# ModuloSlave.net
KiCad netlist of a schematic drawn in EAGLE
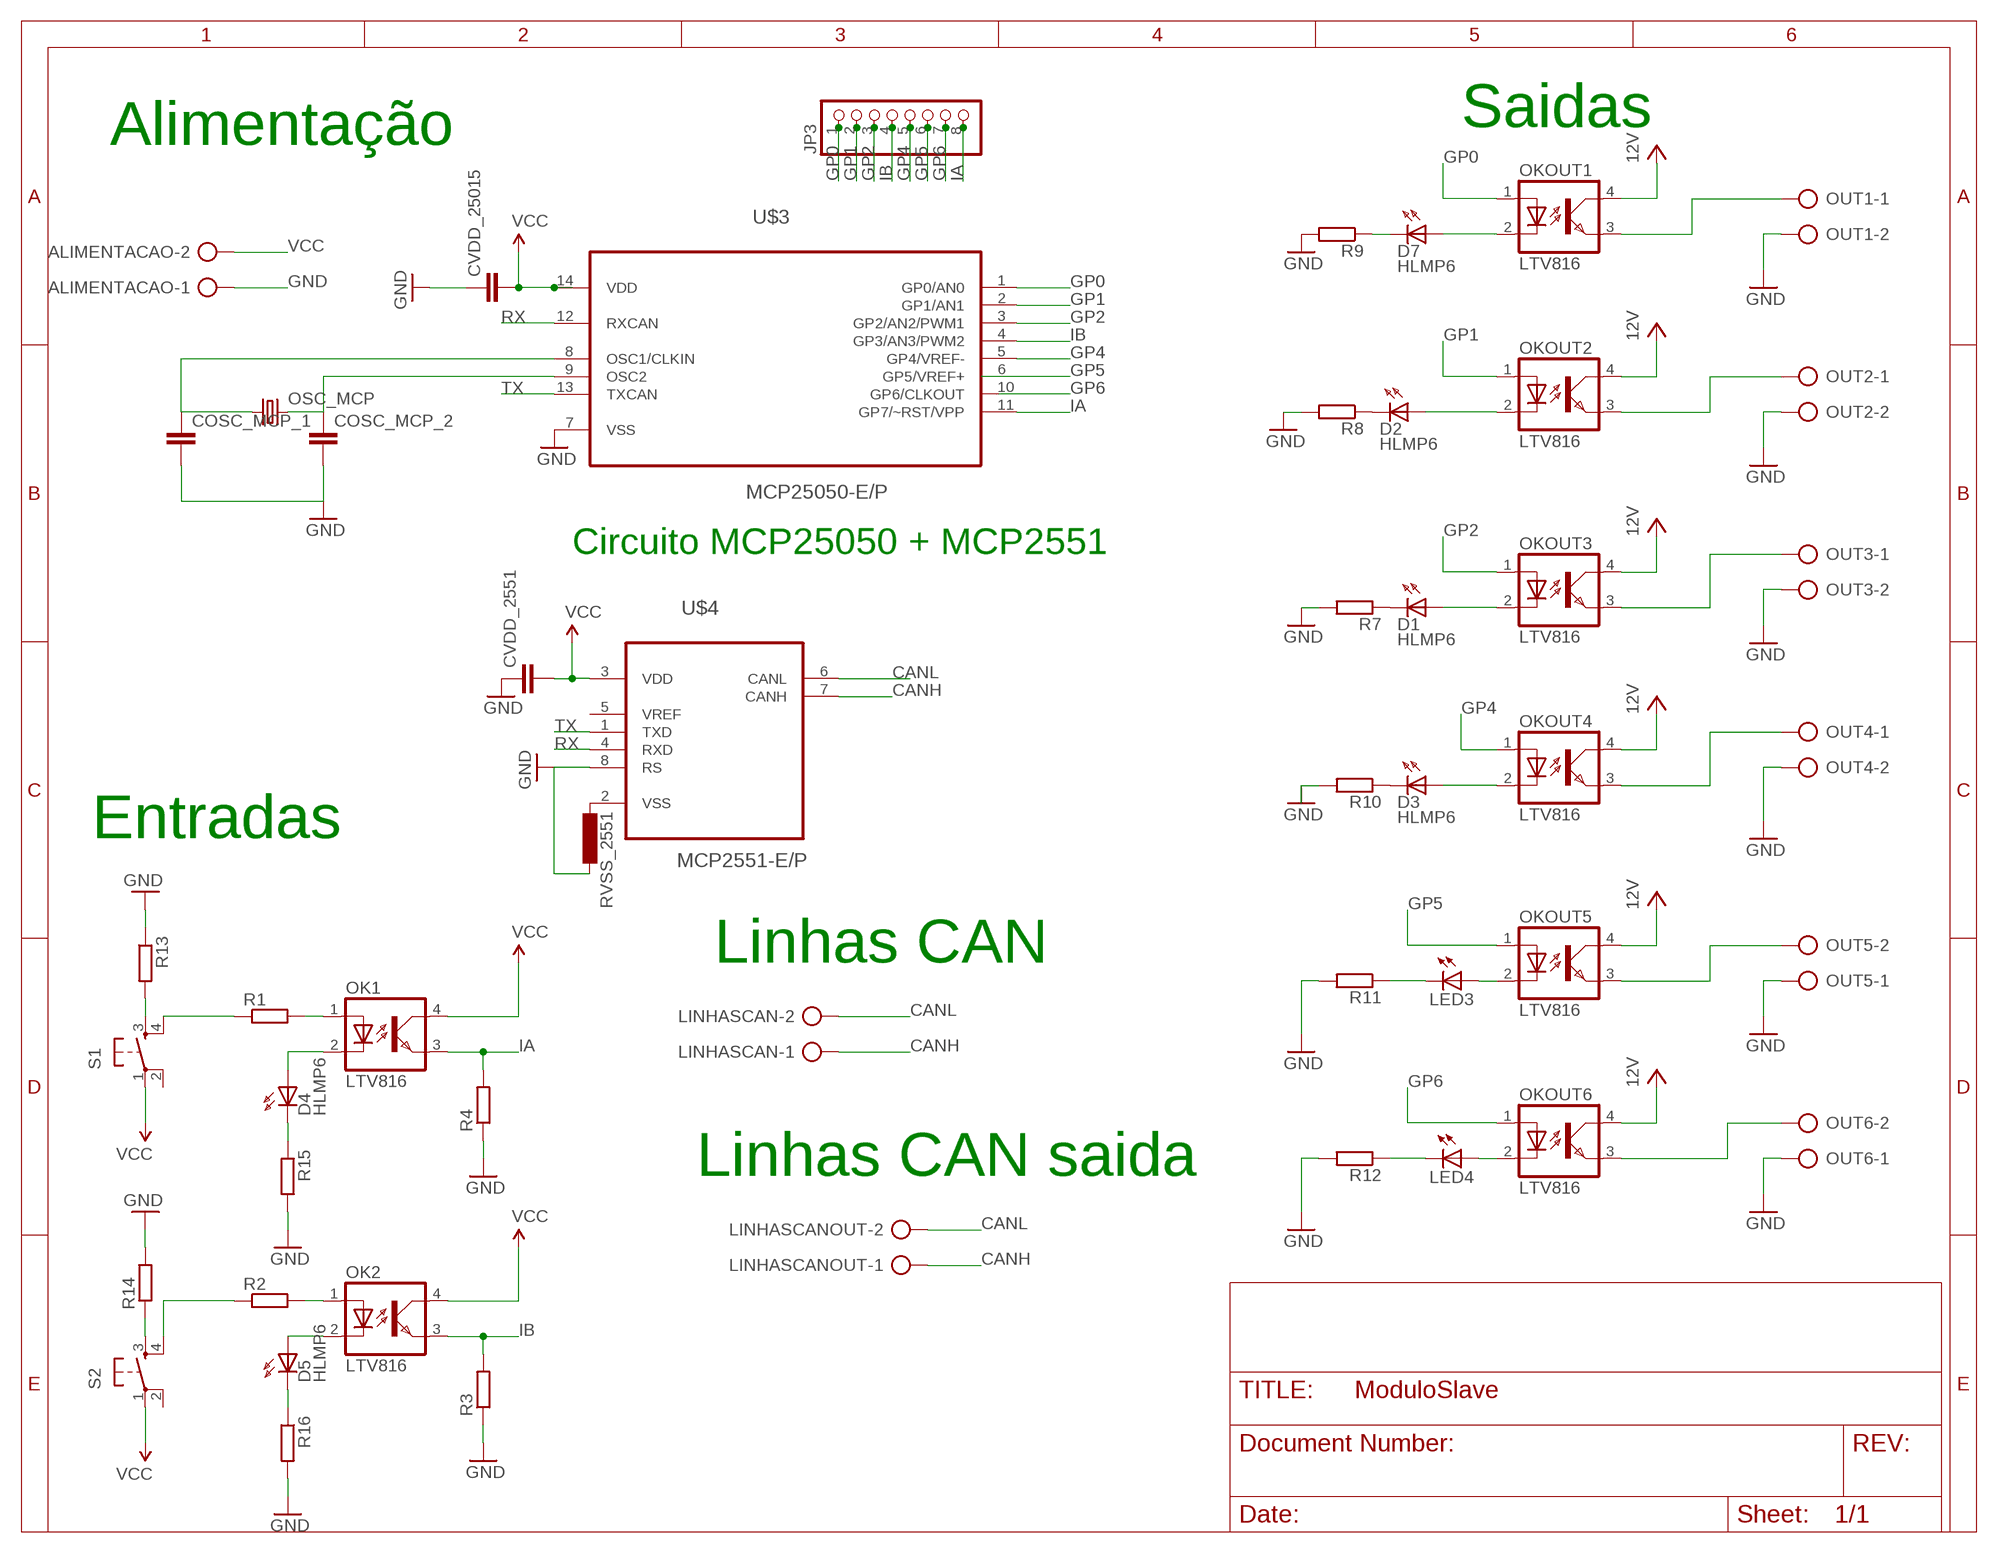
[diagram p0: schematic, sheet 1]

(export (version "E")
  (design (tool "Eeschema 10.0.6"))
  (components
    (comp (ref "ALIMENTACAO")
      (value "AK300/2")
      (footprint "eagle-import:AK300_2")
      (libsource (lib "eagle-import") (part "AK300/2"))
    )
    (comp (ref "COSC_MCP_1")
      (value "CAP_")
      (footprint "eagle-import:AXIAL-5MM")
      (libsource (lib "eagle-import") (part "CAP_"))
    )
    (comp (ref "COSC_MCP_2")
      (value "CAP_")
      (footprint "eagle-import:AXIAL-5MM")
      (libsource (lib "eagle-import") (part "CAP_"))
    )
    (comp (ref "CVDD_2551")
      (value "CAP_")
      (footprint "eagle-import:AXIAL-5MM")
      (libsource (lib "eagle-import") (part "CAP_"))
    )
    (comp (ref "CVDD_25015")
      (value "CAP_")
      (footprint "eagle-import:AXIAL-5MM")
      (libsource (lib "eagle-import") (part "CAP_"))
    )
    (comp (ref "D1")
      (value "HLMP6")
      (footprint "eagle-import:HLMP6")
      (fields (field (name "MF") "AGILENT TECHNOLOGIES") (field (name "MPN") "HLMP-6500"))
      (libsource (lib "eagle-import") (part "HLMP6"))
    )
    (comp (ref "D2")
      (value "HLMP6")
      (footprint "eagle-import:HLMP6")
      (fields (field (name "MF") "AGILENT TECHNOLOGIES") (field (name "MPN") "HLMP-6500"))
      (libsource (lib "eagle-import") (part "HLMP6"))
    )
    (comp (ref "D3")
      (value "HLMP6")
      (footprint "eagle-import:HLMP6")
      (fields (field (name "MF") "AGILENT TECHNOLOGIES") (field (name "MPN") "HLMP-6500"))
      (libsource (lib "eagle-import") (part "HLMP6"))
    )
    (comp (ref "D4")
      (value "HLMP6")
      (footprint "eagle-import:HLMP6")
      (fields (field (name "MF") "AGILENT TECHNOLOGIES") (field (name "MPN") "HLMP-6500"))
      (libsource (lib "eagle-import") (part "HLMP6"))
    )
    (comp (ref "D5")
      (value "HLMP6")
      (footprint "eagle-import:HLMP6")
      (fields (field (name "MF") "AGILENT TECHNOLOGIES") (field (name "MPN") "HLMP-6500"))
      (libsource (lib "eagle-import") (part "HLMP6"))
    )
    (comp (ref "D7")
      (value "HLMP6")
      (footprint "eagle-import:HLMP6")
      (fields (field (name "MF") "AGILENT TECHNOLOGIES") (field (name "MPN") "HLMP-6500"))
      (libsource (lib "eagle-import") (part "HLMP6"))
    )
    (comp (ref "JP3")
      (value "PINHD-1X8")
      (footprint "eagle-import:1X08")
      (libsource (lib "eagle-import") (part "PINHD-1X8"))
    )
    (comp (ref "LED3")
      (value "LED_E")
      (footprint "eagle-import:LED_1206")
      (libsource (lib "eagle-import") (part "LED_E"))
    )
    (comp (ref "LED4")
      (value "LED_E")
      (footprint "eagle-import:LED_1206")
      (libsource (lib "eagle-import") (part "LED_E"))
    )
    (comp (ref "LINHASCAN")
      (value "AK300/2")
      (footprint "eagle-import:AK300_2")
      (libsource (lib "eagle-import") (part "AK300/2"))
    )
    (comp (ref "LINHASCANOUT")
      (value "AK300/2")
      (footprint "eagle-import:AK300_2")
      (libsource (lib "eagle-import") (part "AK300/2"))
    )
    (comp (ref "OK1")
      (value "LTV816")
      (footprint "eagle-import:DIL04")
      (libsource (lib "eagle-import") (part "LTV816"))
    )
    (comp (ref "OK2")
      (value "LTV816")
      (footprint "eagle-import:DIL04")
      (libsource (lib "eagle-import") (part "LTV816"))
    )
    (comp (ref "OKOUT1")
      (value "LTV816")
      (footprint "eagle-import:DIL04")
      (libsource (lib "eagle-import") (part "LTV816"))
    )
    (comp (ref "OKOUT2")
      (value "LTV816")
      (footprint "eagle-import:DIL04")
      (libsource (lib "eagle-import") (part "LTV816"))
    )
    (comp (ref "OKOUT3")
      (value "LTV816")
      (footprint "eagle-import:DIL04")
      (libsource (lib "eagle-import") (part "LTV816"))
    )
    (comp (ref "OKOUT4")
      (value "LTV816")
      (footprint "eagle-import:DIL04")
      (libsource (lib "eagle-import") (part "LTV816"))
    )
    (comp (ref "OKOUT5")
      (value "LTV816")
      (footprint "eagle-import:DIL04")
      (libsource (lib "eagle-import") (part "LTV816"))
    )
    (comp (ref "OKOUT6")
      (value "LTV816")
      (footprint "eagle-import:DIL04")
      (libsource (lib "eagle-import") (part "LTV816"))
    )
    (comp (ref "OSC_MCP")
      (value "CRYSTALHC49S")
      (footprint "eagle-import:HC49_S")
      (libsource (lib "eagle-import") (part "CRYSTALHC49S"))
    )
    (comp (ref "OUT1")
      (value "AK300/2")
      (footprint "eagle-import:AK300_2")
      (libsource (lib "eagle-import") (part "AK300/2"))
    )
    (comp (ref "OUT2")
      (value "AK300/2")
      (footprint "eagle-import:AK300_2")
      (libsource (lib "eagle-import") (part "AK300/2"))
    )
    (comp (ref "OUT3")
      (value "AK300/2")
      (footprint "eagle-import:AK300_2")
      (libsource (lib "eagle-import") (part "AK300/2"))
    )
    (comp (ref "OUT4")
      (value "AK300/2")
      (footprint "eagle-import:AK300_2")
      (libsource (lib "eagle-import") (part "AK300/2"))
    )
    (comp (ref "OUT5")
      (value "AK300/2")
      (footprint "eagle-import:AK300_2")
      (libsource (lib "eagle-import") (part "AK300/2"))
    )
    (comp (ref "OUT6")
      (value "AK300/2")
      (footprint "eagle-import:AK300_2")
      (libsource (lib "eagle-import") (part "AK300/2"))
    )
    (comp (ref "R1")
      (value "R-EU_0204/5")
      (footprint "eagle-import:0204_5")
      (libsource (lib "eagle-import") (part "R-EU_0204/5"))
    )
    (comp (ref "R2")
      (value "R-EU_0204/5")
      (footprint "eagle-import:0204_5")
      (libsource (lib "eagle-import") (part "R-EU_0204/5"))
    )
    (comp (ref "R3")
      (value "R-EU_0204/5")
      (footprint "eagle-import:0204_5")
      (libsource (lib "eagle-import") (part "R-EU_0204/5"))
    )
    (comp (ref "R4")
      (value "R-EU_0204/5")
      (footprint "eagle-import:0204_5")
      (libsource (lib "eagle-import") (part "R-EU_0204/5"))
    )
    (comp (ref "R7")
      (value "R-EU_0204/5")
      (footprint "eagle-import:0204_5")
      (libsource (lib "eagle-import") (part "R-EU_0204/5"))
    )
    (comp (ref "R8")
      (value "R-EU_0204/5")
      (footprint "eagle-import:0204_5")
      (libsource (lib "eagle-import") (part "R-EU_0204/5"))
    )
    (comp (ref "R9")
      (value "R-EU_0204/5")
      (footprint "eagle-import:0204_5")
      (libsource (lib "eagle-import") (part "R-EU_0204/5"))
    )
    (comp (ref "R10")
      (value "R-EU_0204/5")
      (footprint "eagle-import:0204_5")
      (libsource (lib "eagle-import") (part "R-EU_0204/5"))
    )
    (comp (ref "R11")
      (value "R-EU_0204/5")
      (footprint "eagle-import:0204_5")
      (libsource (lib "eagle-import") (part "R-EU_0204/5"))
    )
    (comp (ref "R12")
      (value "R-EU_0204/5")
      (footprint "eagle-import:0204_5")
      (libsource (lib "eagle-import") (part "R-EU_0204/5"))
    )
    (comp (ref "R13")
      (value "R-EU_0204/5")
      (footprint "eagle-import:0204_5")
      (libsource (lib "eagle-import") (part "R-EU_0204/5"))
    )
    (comp (ref "R14")
      (value "R-EU_0204/5")
      (footprint "eagle-import:0204_5")
      (libsource (lib "eagle-import") (part "R-EU_0204/5"))
    )
    (comp (ref "R15")
      (value "R-EU_0204/5")
      (footprint "eagle-import:0204_5")
      (libsource (lib "eagle-import") (part "R-EU_0204/5"))
    )
    (comp (ref "R16")
      (value "R-EU_0204/5")
      (footprint "eagle-import:0204_5")
      (libsource (lib "eagle-import") (part "R-EU_0204/5"))
    )
    (comp (ref "RVSS_2551")
      (value "L-EU0204V")
      (footprint "eagle-import:0204V")
      (libsource (lib "eagle-import") (part "L-EU0204V"))
    )
    (comp (ref "S1")
      (value "TAC_SWITCHPTH")
      (footprint "eagle-import:TACTILE-PTH")
      (libsource (lib "eagle-import") (part "TAC_SWITCHPTH"))
    )
    (comp (ref "S2")
      (value "TAC_SWITCHPTH")
      (footprint "eagle-import:TACTILE-PTH")
      (libsource (lib "eagle-import") (part "TAC_SWITCHPTH"))
    )
    (comp (ref "U$3")
      (value "MCP25050-E/P")
      (footprint "eagle-import:DIP254P762X432-14")
      (libsource (lib "eagle-import") (part "MCP25050-E/P"))
    )
    (comp (ref "U$4")
      (value "MCP2551-E/P")
      (footprint "eagle-import:DIP254P762X432-8")
      (libsource (lib "eagle-import") (part "MCP2551-E/P"))
    )
  )
  (nets
    (net (code "1") (name "/CANH") (class "Default")
      (node (ref "LINHASCAN") (pin "1") (pinfunction "KL_1") (pintype "passive"))
      (node (ref "LINHASCANOUT") (pin "1") (pinfunction "KL_1") (pintype "passive"))
      (node (ref "U$4") (pin "7") (pinfunction "CANH_7") (pintype "output"))
    )
    (net (code "2") (name "/CANL") (class "Default")
      (node (ref "LINHASCAN") (pin "2") (pinfunction "KL_2") (pintype "passive"))
      (node (ref "LINHASCANOUT") (pin "2") (pinfunction "KL_2") (pintype "passive"))
      (node (ref "U$4") (pin "6") (pinfunction "CANL_6") (pintype "output"))
    )
    (net (code "3") (name "/GP0") (class "Default")
      (node (ref "JP3") (pin "1") (pinfunction "1_1") (pintype "passive"))
      (node (ref "OKOUT1") (pin "1") (pinfunction "A_1") (pintype "passive"))
      (node (ref "U$3") (pin "1") (pinfunction "GP0/AN0_1") (pintype "bidirectional"))
    )
    (net (code "4") (name "/GP1") (class "Default")
      (node (ref "JP3") (pin "2") (pinfunction "2_2") (pintype "passive"))
      (node (ref "OKOUT2") (pin "1") (pinfunction "A_1") (pintype "passive"))
      (node (ref "U$3") (pin "2") (pinfunction "GP1/AN1_2") (pintype "bidirectional"))
    )
    (net (code "5") (name "/GP2") (class "Default")
      (node (ref "JP3") (pin "3") (pinfunction "3_3") (pintype "passive"))
      (node (ref "OKOUT3") (pin "1") (pinfunction "A_1") (pintype "passive"))
      (node (ref "U$3") (pin "3") (pinfunction "GP2/AN2/PWM1_3") (pintype "bidirectional"))
    )
    (net (code "6") (name "/GP4") (class "Default")
      (node (ref "JP3") (pin "5") (pinfunction "5_5") (pintype "passive"))
      (node (ref "OKOUT4") (pin "1") (pinfunction "A_1") (pintype "passive"))
      (node (ref "U$3") (pin "5") (pinfunction "GP4/VREF-_5") (pintype "bidirectional"))
    )
    (net (code "7") (name "/GP5") (class "Default")
      (node (ref "JP3") (pin "6") (pinfunction "6_6") (pintype "passive"))
      (node (ref "OKOUT5") (pin "1") (pinfunction "A_1") (pintype "passive"))
    )
    (net (code "8") (name "/GP6") (class "Default")
      (node (ref "JP3") (pin "7") (pinfunction "7_7") (pintype "passive"))
      (node (ref "OKOUT6") (pin "1") (pinfunction "A_1") (pintype "passive"))
    )
    (net (code "9") (name "/IA") (class "Default")
      (node (ref "JP3") (pin "8") (pinfunction "8_8") (pintype "passive"))
      (node (ref "OK1") (pin "3") (pinfunction "EMIT_3") (pintype "passive"))
      (node (ref "R4") (pin "2") (pinfunction "2_2") (pintype "passive"))
      (node (ref "U$3") (pin "11") (pinfunction "GP7/~{RST/VPP}_11") (pintype "bidirectional"))
    )
    (net (code "10") (name "/IB") (class "Default")
      (node (ref "JP3") (pin "4") (pinfunction "4_4") (pintype "passive"))
      (node (ref "OK2") (pin "3") (pinfunction "EMIT_3") (pintype "passive"))
      (node (ref "R3") (pin "2") (pinfunction "2_2") (pintype "passive"))
      (node (ref "U$3") (pin "4") (pinfunction "GP3/AN3/PWM2_4") (pintype "bidirectional"))
    )
    (net (code "11") (name "/RX") (class "Default")
      (node (ref "U$3") (pin "12") (pinfunction "RXCAN_12") (pintype "input"))
      (node (ref "U$4") (pin "4") (pinfunction "RXD_4") (pintype "input"))
    )
    (net (code "12") (name "/TX") (class "Default")
      (node (ref "U$3") (pin "13") (pinfunction "TXCAN_13") (pintype "output"))
      (node (ref "U$4") (pin "1") (pinfunction "TXD_1") (pintype "input"))
    )
    (net (code "13") (name "12V") (class "Default")
      (node (ref "ALIMENTACAO") (pin "2") (pinfunction "KL_2") (pintype "passive"))
      (node (ref "CVDD_25015") (pin "P$2") (pinfunction "2_P$2") (pintype "passive"))
      (node (ref "CVDD_2551") (pin "P$2") (pinfunction "2_P$2") (pintype "passive"))
      (node (ref "OK1") (pin "4") (pinfunction "COL_4") (pintype "passive"))
      (node (ref "OK2") (pin "4") (pinfunction "COL_4") (pintype "passive"))
      (node (ref "OKOUT1") (pin "4") (pinfunction "COL_4") (pintype "passive"))
      (node (ref "OKOUT2") (pin "4") (pinfunction "COL_4") (pintype "passive"))
      (node (ref "OKOUT3") (pin "4") (pinfunction "COL_4") (pintype "passive"))
      (node (ref "OKOUT4") (pin "4") (pinfunction "COL_4") (pintype "passive"))
      (node (ref "OKOUT5") (pin "4") (pinfunction "COL_4") (pintype "passive"))
      (node (ref "OKOUT6") (pin "4") (pinfunction "COL_4") (pintype "passive"))
      (node (ref "S1") (pin "1") (pinfunction "1_1") (pintype "passive"))
      (node (ref "S2") (pin "1") (pinfunction "1_1") (pintype "passive"))
      (node (ref "U$3") (pin "14") (pinfunction "VDD_14") (pintype "power_in"))
      (node (ref "U$4") (pin "3") (pinfunction "VDD_3") (pintype "power_in"))
    )
    (net (code "14") (name "GND") (class "Default")
      (node (ref "ALIMENTACAO") (pin "1") (pinfunction "KL_1") (pintype "passive"))
      (node (ref "COSC_MCP_1") (pin "P$2") (pinfunction "2_P$2") (pintype "passive"))
      (node (ref "COSC_MCP_2") (pin "P$2") (pinfunction "2_P$2") (pintype "passive"))
      (node (ref "CVDD_25015") (pin "P$1") (pinfunction "1_P$1") (pintype "passive"))
      (node (ref "CVDD_2551") (pin "P$1") (pinfunction "1_P$1") (pintype "passive"))
      (node (ref "OUT1") (pin "2") (pinfunction "KL_2") (pintype "passive"))
      (node (ref "OUT2") (pin "2") (pinfunction "KL_2") (pintype "passive"))
      (node (ref "OUT3") (pin "2") (pinfunction "KL_2") (pintype "passive"))
      (node (ref "OUT4") (pin "2") (pinfunction "KL_2") (pintype "passive"))
      (node (ref "OUT5") (pin "1") (pinfunction "KL_1") (pintype "passive"))
      (node (ref "OUT6") (pin "1") (pinfunction "KL_1") (pintype "passive"))
      (node (ref "R10") (pin "2") (pinfunction "2_2") (pintype "passive"))
      (node (ref "R11") (pin "2") (pinfunction "2_2") (pintype "passive"))
      (node (ref "R12") (pin "2") (pinfunction "2_2") (pintype "passive"))
      (node (ref "R13") (pin "1") (pinfunction "1_1") (pintype "passive"))
      (node (ref "R14") (pin "2") (pinfunction "2_2") (pintype "passive"))
      (node (ref "R15") (pin "2") (pinfunction "2_2") (pintype "passive"))
      (node (ref "R16") (pin "2") (pinfunction "2_2") (pintype "passive"))
      (node (ref "R3") (pin "1") (pinfunction "1_1") (pintype "passive"))
      (node (ref "R4") (pin "1") (pinfunction "1_1") (pintype "passive"))
      (node (ref "R7") (pin "2") (pinfunction "2_2") (pintype "passive"))
      (node (ref "R8") (pin "2") (pinfunction "2_2") (pintype "passive"))
      (node (ref "R9") (pin "2") (pinfunction "2_2") (pintype "passive"))
      (node (ref "RVSS_2551") (pin "1") (pinfunction "1_1") (pintype "passive"))
      (node (ref "U$3") (pin "7") (pinfunction "VSS_7") (pintype "power_in"))
      (node (ref "U$4") (pin "8") (pinfunction "RS_8") (pintype "input"))
    )
    (net (code "15") (name "Net-(COSC_MCP_1-1)") (class "Default")
      (node (ref "COSC_MCP_1") (pin "P$1") (pinfunction "1_P$1") (pintype "passive"))
      (node (ref "OSC_MCP") (pin "1") (pinfunction "1_1") (pintype "passive"))
      (node (ref "U$3") (pin "8") (pinfunction "OSC1/CLKIN_8") (pintype "bidirectional"))
    )
    (net (code "16") (name "Net-(COSC_MCP_2-1)") (class "Default")
      (node (ref "COSC_MCP_2") (pin "P$1") (pinfunction "1_P$1") (pintype "passive"))
      (node (ref "OSC_MCP") (pin "2") (pinfunction "2_2") (pintype "passive"))
      (node (ref "U$3") (pin "9") (pinfunction "OSC2_9") (pintype "bidirectional"))
    )
    (net (code "17") (name "Net-(D1-PadK)") (class "Default")
      (node (ref "D1") (pin "K") (pinfunction "K_K") (pintype "passive"))
      (node (ref "R7") (pin "1") (pinfunction "1_1") (pintype "passive"))
    )
    (net (code "18") (name "Net-(D2-PadK)") (class "Default")
      (node (ref "D2") (pin "K") (pinfunction "K_K") (pintype "passive"))
      (node (ref "R8") (pin "1") (pinfunction "1_1") (pintype "passive"))
    )
    (net (code "19") (name "Net-(D3-PadK)") (class "Default")
      (node (ref "D3") (pin "K") (pinfunction "K_K") (pintype "passive"))
      (node (ref "R10") (pin "1") (pinfunction "1_1") (pintype "passive"))
    )
    (net (code "20") (name "Net-(D4-PadK)") (class "Default")
      (node (ref "D4") (pin "K") (pinfunction "K_K") (pintype "passive"))
      (node (ref "R15") (pin "1") (pinfunction "1_1") (pintype "passive"))
    )
    (net (code "21") (name "Net-(D5-PadK)") (class "Default")
      (node (ref "D5") (pin "K") (pinfunction "K_K") (pintype "passive"))
      (node (ref "R16") (pin "1") (pinfunction "1_1") (pintype "passive"))
    )
    (net (code "22") (name "Net-(D7-PadK)") (class "Default")
      (node (ref "D7") (pin "K") (pinfunction "K_K") (pintype "passive"))
      (node (ref "R9") (pin "1") (pinfunction "1_1") (pintype "passive"))
    )
    (net (code "23") (name "Net-(LED3-PadC)") (class "Default")
      (node (ref "LED3") (pin "C") (pinfunction "C_C") (pintype "passive"))
      (node (ref "R11") (pin "1") (pinfunction "1_1") (pintype "passive"))
    )
    (net (code "24") (name "Net-(LED4-PadC)") (class "Default")
      (node (ref "LED4") (pin "C") (pinfunction "C_C") (pintype "passive"))
      (node (ref "R12") (pin "1") (pinfunction "1_1") (pintype "passive"))
    )
    (net (code "25") (name "Net-(OK1-A)") (class "Default")
      (node (ref "OK1") (pin "1") (pinfunction "A_1") (pintype "passive"))
      (node (ref "R1") (pin "2") (pinfunction "2_2") (pintype "passive"))
    )
    (net (code "26") (name "Net-(OK1-C)") (class "Default")
      (node (ref "D4") (pin "A") (pinfunction "A_A") (pintype "passive"))
      (node (ref "OK1") (pin "2") (pinfunction "C_2") (pintype "passive"))
    )
    (net (code "27") (name "Net-(OK2-A)") (class "Default")
      (node (ref "OK2") (pin "1") (pinfunction "A_1") (pintype "passive"))
      (node (ref "R2") (pin "2") (pinfunction "2_2") (pintype "passive"))
    )
    (net (code "28") (name "Net-(OK2-C)") (class "Default")
      (node (ref "D5") (pin "A") (pinfunction "A_A") (pintype "passive"))
      (node (ref "OK2") (pin "2") (pinfunction "C_2") (pintype "passive"))
    )
    (net (code "29") (name "Net-(OKOUT1-C)") (class "Default")
      (node (ref "D7") (pin "A") (pinfunction "A_A") (pintype "passive"))
      (node (ref "OKOUT1") (pin "2") (pinfunction "C_2") (pintype "passive"))
    )
    (net (code "30") (name "Net-(OKOUT1-EMIT)") (class "Default")
      (node (ref "OKOUT1") (pin "3") (pinfunction "EMIT_3") (pintype "passive"))
      (node (ref "OUT1") (pin "1") (pinfunction "KL_1") (pintype "passive"))
    )
    (net (code "31") (name "Net-(OKOUT2-C)") (class "Default")
      (node (ref "D2") (pin "A") (pinfunction "A_A") (pintype "passive"))
      (node (ref "OKOUT2") (pin "2") (pinfunction "C_2") (pintype "passive"))
    )
    (net (code "32") (name "Net-(OKOUT2-EMIT)") (class "Default")
      (node (ref "OKOUT2") (pin "3") (pinfunction "EMIT_3") (pintype "passive"))
      (node (ref "OUT2") (pin "1") (pinfunction "KL_1") (pintype "passive"))
    )
    (net (code "33") (name "Net-(OKOUT3-C)") (class "Default")
      (node (ref "D1") (pin "A") (pinfunction "A_A") (pintype "passive"))
      (node (ref "OKOUT3") (pin "2") (pinfunction "C_2") (pintype "passive"))
    )
    (net (code "34") (name "Net-(OKOUT3-EMIT)") (class "Default")
      (node (ref "OKOUT3") (pin "3") (pinfunction "EMIT_3") (pintype "passive"))
      (node (ref "OUT3") (pin "1") (pinfunction "KL_1") (pintype "passive"))
    )
    (net (code "35") (name "Net-(OKOUT4-C)") (class "Default")
      (node (ref "D3") (pin "A") (pinfunction "A_A") (pintype "passive"))
      (node (ref "OKOUT4") (pin "2") (pinfunction "C_2") (pintype "passive"))
    )
    (net (code "36") (name "Net-(OKOUT4-EMIT)") (class "Default")
      (node (ref "OKOUT4") (pin "3") (pinfunction "EMIT_3") (pintype "passive"))
      (node (ref "OUT4") (pin "1") (pinfunction "KL_1") (pintype "passive"))
    )
    (net (code "37") (name "Net-(OKOUT5-C)") (class "Default")
      (node (ref "LED3") (pin "A") (pinfunction "A_A") (pintype "passive"))
      (node (ref "OKOUT5") (pin "2") (pinfunction "C_2") (pintype "passive"))
    )
    (net (code "38") (name "Net-(OKOUT5-EMIT)") (class "Default")
      (node (ref "OKOUT5") (pin "3") (pinfunction "EMIT_3") (pintype "passive"))
      (node (ref "OUT5") (pin "2") (pinfunction "KL_2") (pintype "passive"))
    )
    (net (code "39") (name "Net-(OKOUT6-C)") (class "Default")
      (node (ref "LED4") (pin "A") (pinfunction "A_A") (pintype "passive"))
      (node (ref "OKOUT6") (pin "2") (pinfunction "C_2") (pintype "passive"))
    )
    (net (code "40") (name "Net-(OKOUT6-EMIT)") (class "Default")
      (node (ref "OKOUT6") (pin "3") (pinfunction "EMIT_3") (pintype "passive"))
      (node (ref "OUT6") (pin "2") (pinfunction "KL_2") (pintype "passive"))
    )
    (net (code "41") (name "Net-(R1-Pad1)") (class "Default")
      (node (ref "R1") (pin "1") (pinfunction "1_1") (pintype "passive"))
      (node (ref "S1") (pin "4") (pinfunction "4_4") (pintype "passive"))
    )
    (net (code "42") (name "Net-(R2-Pad1)") (class "Default")
      (node (ref "R2") (pin "1") (pinfunction "1_1") (pintype "passive"))
      (node (ref "S2") (pin "4") (pinfunction "4_4") (pintype "passive"))
    )
    (net (code "43") (name "Net-(R13-Pad2)") (class "Default")
      (node (ref "R13") (pin "2") (pinfunction "2_2") (pintype "passive"))
      (node (ref "S1") (pin "3") (pinfunction "3_3") (pintype "passive"))
    )
    (net (code "44") (name "Net-(R14-Pad1)") (class "Default")
      (node (ref "R14") (pin "1") (pinfunction "1_1") (pintype "passive"))
      (node (ref "S2") (pin "3") (pinfunction "3_3") (pintype "passive"))
    )
    (net (code "45") (name "Net-(U$4-VSS)") (class "Default")
      (node (ref "RVSS_2551") (pin "2") (pinfunction "2_2") (pintype "passive"))
      (node (ref "U$4") (pin "2") (pinfunction "VSS_2") (pintype "passive"))
    )
    (net (code "46") (name "unconnected-(S1-Pad2)") (class "Default")
      (node (ref "S1") (pin "2") (pinfunction "2_2") (pintype "passive"))
    )
    (net (code "47") (name "unconnected-(S2-Pad2)") (class "Default")
      (node (ref "S2") (pin "2") (pinfunction "2_2") (pintype "passive"))
    )
    (net (code "48") (name "unconnected-(U$3-GP5{slash}VREF+-Pad6)") (class "Default")
      (node (ref "U$3") (pin "6") (pinfunction "GP5/VREF+_6") (pintype "bidirectional"))
    )
    (net (code "49") (name "unconnected-(U$3-GP6{slash}CLKOUT-Pad10)") (class "Default")
      (node (ref "U$3") (pin "10") (pinfunction "GP6/CLKOUT_10") (pintype "bidirectional"))
    )
    (net (code "50") (name "unconnected-(U$4-VREF-Pad5)") (class "Default")
      (node (ref "U$4") (pin "5") (pinfunction "VREF_5") (pintype "input"))
    )
  )
)
